# LEDCyrWheel.net
KiCad netlist of a schematic drawn in EAGLE
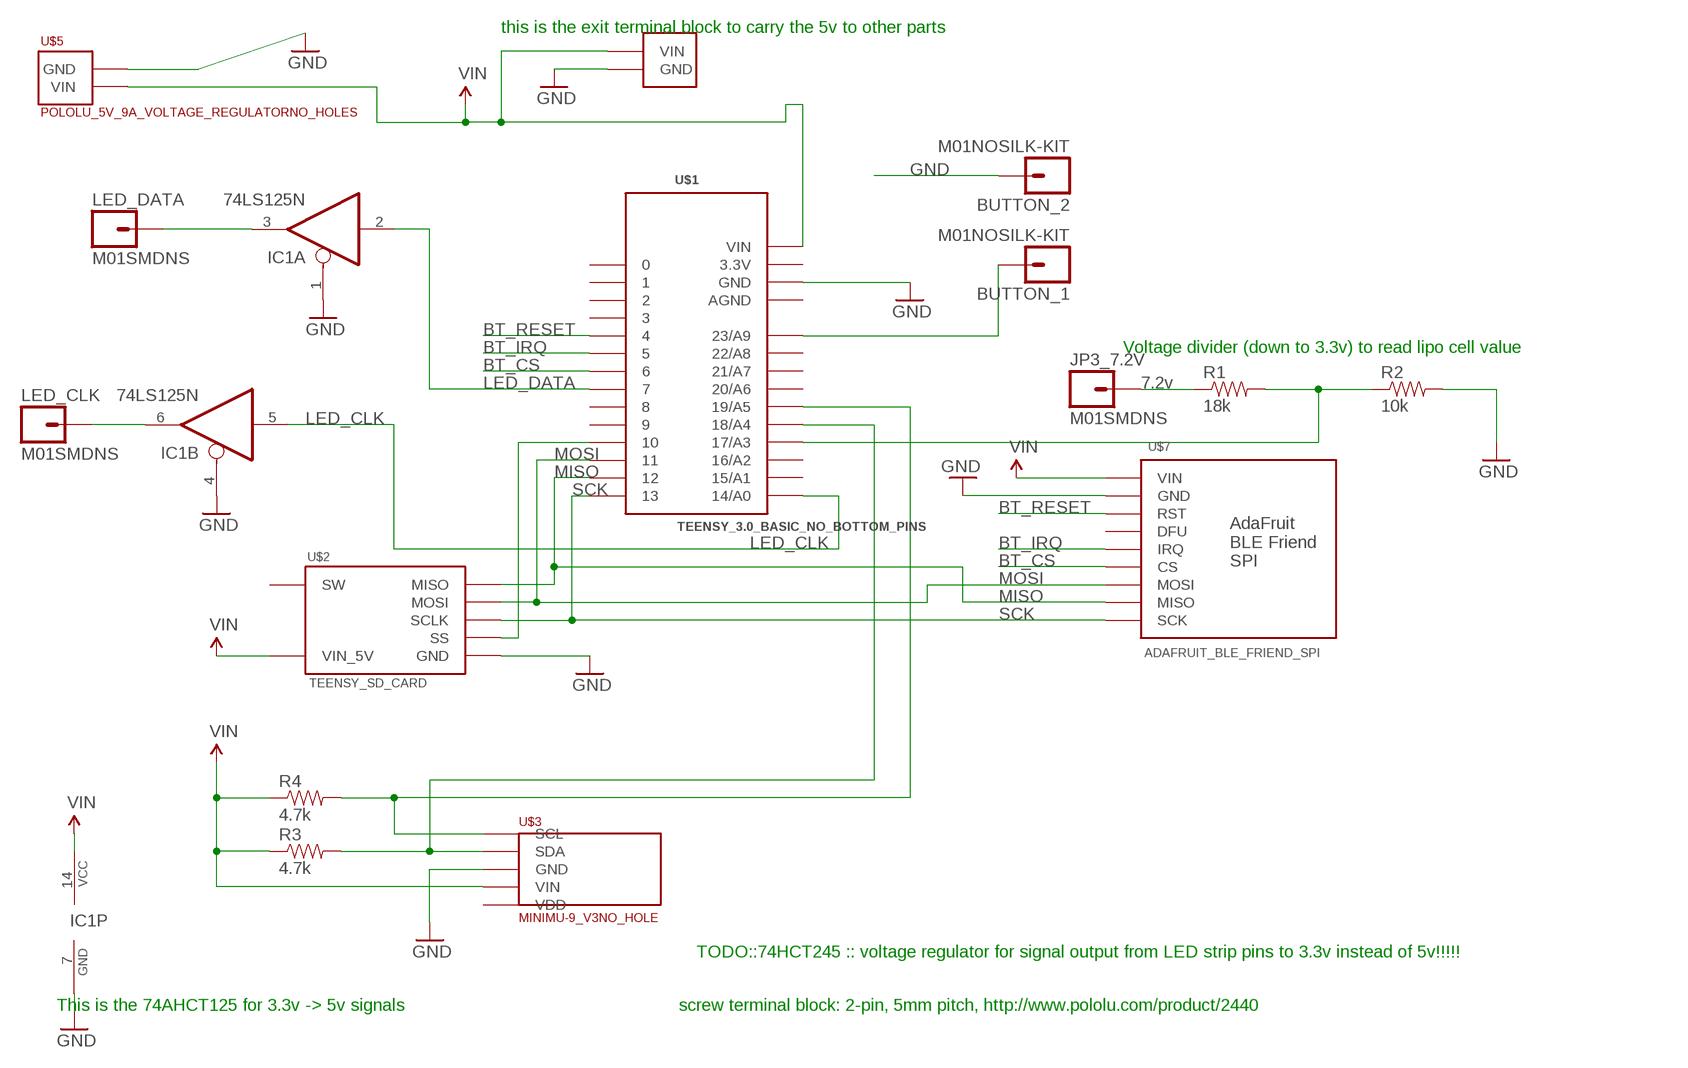
[diagram p0: schematic, sheet 1]

(export (version "E")
  (design (tool "Eeschema 10.0.6"))
  (components
    (comp (ref "BUTTON_1")
      (value "M01NOSILK-KIT")
      (footprint "eagle-import:1X01NS-KIT")
      (libsource (lib "eagle-import") (part "M01NOSILK-KIT"))
    )
    (comp (ref "BUTTON_2")
      (value "M01NOSILK-KIT")
      (footprint "eagle-import:1X01NS-KIT")
      (libsource (lib "eagle-import") (part "M01NOSILK-KIT"))
    )
    (comp (ref "IC1")
      (value "74LS125N")
      (footprint "eagle-import:DIL14")
      (libsource (lib "eagle-import") (part "74125NLS"))
    )
    (comp (ref "JP3_7.2V")
      (value "M01SMDNS")
      (footprint "eagle-import:1X01NS")
      (fields (field (name "VOLTAGE") "7.2v"))
      (libsource (lib "eagle-import") (part "M01SMDNS"))
    )
    (comp (ref "LED_CLK")
      (value "M01SMDNS")
      (footprint "eagle-import:1X01NS")
      (libsource (lib "eagle-import") (part "M01SMDNS"))
    )
    (comp (ref "LED_DATA")
      (value "M01SMDNS")
      (footprint "eagle-import:1X01NS")
      (libsource (lib "eagle-import") (part "M01SMDNS"))
    )
    (comp (ref "R1")
      (value "18k")
      (footprint "eagle-import:AXIAL-0.4")
      (libsource (lib "eagle-import") (part "RESISTORPTH-1/4W"))
    )
    (comp (ref "R2")
      (value "10k")
      (footprint "eagle-import:AXIAL-0.4")
      (libsource (lib "eagle-import") (part "RESISTORPTH-1/4W"))
    )
    (comp (ref "R3")
      (value "4.7k")
      (footprint "eagle-import:AXIAL-0.4")
      (libsource (lib "eagle-import") (part "RESISTORPTH-1/4W"))
    )
    (comp (ref "R4")
      (value "4.7k")
      (footprint "eagle-import:AXIAL-0.4")
      (libsource (lib "eagle-import") (part "RESISTORPTH-1/4W"))
    )
    (comp (ref "U$1")
      (value "TEENSY_3.0_BASIC_NO_BOTTOM_PINS")
      (footprint "eagle-import:TEENSY_3.0_BASIC_NO_BOTTOM_PINS")
      (libsource (lib "eagle-import") (part "TEENSY_3.0_BASIC_NO_BOTTOM_PINS"))
    )
    (comp (ref "U$2")
      (value "TEENSY_SD_CARD")
      (footprint "eagle-import:TEENSY_SD_CARD")
      (libsource (lib "eagle-import") (part "TEENSY_SD_CARD"))
    )
    (comp (ref "U$3")
      (value "MINIMU-9_V3NO_HOLE")
      (footprint "eagle-import:MINIMU-9_V3_NO_HOLE")
      (libsource (lib "eagle-import") (part "MINIMU-9_V3NO_HOLE"))
    )
    (comp (ref "U$5")
      (value "POLOLU_5V_9A_VOLTAGE_REGULATORNO_HOLES")
      (footprint "eagle-import:POLOLU_5V_9A_VOLTAGE_REGULATOR_NO_HOLES")
      (libsource (lib "eagle-import") (part "POLOLU_5V_9A_VOLTAGE_REGULATORNO_HOLES"))
    )
    (comp (ref "U$6")
      (value "VIN_GND_HOLE")
      (footprint "eagle-import:VIN_HOLE")
      (libsource (lib "eagle-import") (part "VIN_GND_HOLE"))
    )
    (comp (ref "U$7")
      (value "ADAFRUIT_BLE_FRIEND_SPI")
      (footprint "eagle-import:ADAFRUIT_BLE_FRIEND_SPI")
      (libsource (lib "eagle-import") (part "ADAFRUIT_BLE_FRIEND_SPI"))
    )
  )
  (nets
    (net (code "1") (name "/3.3V") (class "Default")
      (node (ref "U$1") (pin "3.3V") (pinfunction "3.3V_3.3V") (pintype "power_in"))
    )
    (net (code "2") (name "/AGND") (class "Default")
      (node (ref "U$1") (pin "AGND") (pinfunction "AGND_AGND") (pintype "power_in"))
    )
    (net (code "3") (name "/BT_CS") (class "Default")
      (node (ref "U$1") (pin "6") (pinfunction "6_6") (pintype "bidirectional"))
      (node (ref "U$7") (pin "CS") (pinfunction "CS_CS") (pintype "bidirectional"))
    )
    (net (code "4") (name "/BT_IRQ") (class "Default")
      (node (ref "U$1") (pin "5") (pinfunction "5_5") (pintype "bidirectional"))
      (node (ref "U$7") (pin "IRQ") (pinfunction "IRQ_IRQ") (pintype "bidirectional"))
    )
    (net (code "5") (name "/BT_RESET") (class "Default")
      (node (ref "U$1") (pin "4") (pinfunction "4_4") (pintype "bidirectional"))
      (node (ref "U$7") (pin "RST") (pinfunction "RST_RST") (pintype "bidirectional"))
    )
    (net (code "6") (name "/LED_CLK") (class "Default")
      (node (ref "IC1") (pin "5") (pinfunction "I_5") (pintype "input"))
      (node (ref "U$1") (pin "14/A0") (pinfunction "14/A0_14/A0") (pintype "bidirectional"))
    )
    (net (code "7") (name "/LED_DATA") (class "Default")
      (node (ref "IC1") (pin "2") (pinfunction "I_2") (pintype "input"))
      (node (ref "U$1") (pin "7") (pinfunction "7_7") (pintype "bidirectional"))
    )
    (net (code "8") (name "/MISO") (class "Default")
      (node (ref "U$1") (pin "12") (pinfunction "12_12") (pintype "bidirectional"))
      (node (ref "U$2") (pin "MISO") (pinfunction "MISO_MISO") (pintype "bidirectional"))
      (node (ref "U$7") (pin "MISO") (pinfunction "MISO_MISO") (pintype "bidirectional"))
    )
    (net (code "9") (name "/MOSI") (class "Default")
      (node (ref "U$1") (pin "11") (pinfunction "11_11") (pintype "bidirectional"))
      (node (ref "U$2") (pin "MOSI") (pinfunction "MOSI_MOSI") (pintype "bidirectional"))
      (node (ref "U$7") (pin "MOSI") (pinfunction "MOSI_MOSI") (pintype "bidirectional"))
    )
    (net (code "10") (name "/SCK") (class "Default")
      (node (ref "U$1") (pin "13") (pinfunction "13_13") (pintype "bidirectional"))
      (node (ref "U$2") (pin "SCLK") (pinfunction "SCLK_SCLK") (pintype "bidirectional"))
      (node (ref "U$7") (pin "SCK") (pinfunction "SCK_SCK") (pintype "bidirectional"))
    )
    (net (code "11") (name "GND") (class "Default")
      (node (ref "BUTTON_2") (pin "1") (pinfunction "1_1") (pintype "passive"))
      (node (ref "IC1") (pin "1") (pinfunction "OE_1") (pintype "input"))
      (node (ref "IC1") (pin "4") (pinfunction "OE_4") (pintype "input"))
      (node (ref "IC1") (pin "7") (pinfunction "GND_7") (pintype "power_in"))
      (node (ref "R2") (pin "P$2") (pinfunction "2_P$2") (pintype "passive"))
      (node (ref "U$1") (pin "GND") (pinfunction "GND_GND") (pintype "power_in"))
      (node (ref "U$2") (pin "GND") (pinfunction "GND_GND") (pintype "power_in"))
      (node (ref "U$3") (pin "GND") (pinfunction "GND_GND") (pintype "power_in"))
      (node (ref "U$5") (pin "GND") (pinfunction "GND_GND") (pintype "power_in"))
      (node (ref "U$5") (pin "GND2") (pinfunction "GND_GND2") (pintype "power_in"))
      (node (ref "U$5") (pin "GND3") (pinfunction "GND_GND3") (pintype "power_in"))
      (node (ref "U$6") (pin "GND") (pinfunction "GND_GND") (pintype "power_in"))
      (node (ref "U$7") (pin "GND") (pinfunction "GND_GND") (pintype "power_in"))
    )
    (net (code "12") (name "Net-(BUTTON_1-Pad1)") (class "Default")
      (node (ref "BUTTON_1") (pin "1") (pinfunction "1_1") (pintype "passive"))
      (node (ref "U$1") (pin "23/A9") (pinfunction "23/A9_23/A9") (pintype "bidirectional"))
    )
    (net (code "13") (name "Net-(IC1A-O)") (class "Default")
      (node (ref "IC1") (pin "3") (pinfunction "O_3") (pintype "tri_state"))
      (node (ref "LED_DATA") (pin "1") (pinfunction "1_1") (pintype "passive"))
    )
    (net (code "14") (name "Net-(IC1B-O)") (class "Default")
      (node (ref "IC1") (pin "6") (pinfunction "O_6") (pintype "tri_state"))
      (node (ref "LED_CLK") (pin "1") (pinfunction "1_1") (pintype "passive"))
    )
    (net (code "15") (name "Net-(R1-1)") (class "Default")
      (node (ref "JP3_7.2V") (pin "1") (pinfunction "1_1") (pintype "passive"))
      (node (ref "R1") (pin "P$1") (pinfunction "1_P$1") (pintype "passive"))
    )
    (net (code "16") (name "Net-(R1-2)") (class "Default")
      (node (ref "R1") (pin "P$2") (pinfunction "2_P$2") (pintype "passive"))
      (node (ref "R2") (pin "P$1") (pinfunction "1_P$1") (pintype "passive"))
      (node (ref "U$1") (pin "17/A3") (pinfunction "17/A3_17/A3") (pintype "bidirectional"))
    )
    (net (code "17") (name "Net-(R3-2)") (class "Default")
      (node (ref "R3") (pin "P$2") (pinfunction "2_P$2") (pintype "passive"))
      (node (ref "U$1") (pin "18/A4") (pinfunction "18/A4_18/A4") (pintype "bidirectional"))
      (node (ref "U$3") (pin "SDA") (pinfunction "SDA_SDA") (pintype "bidirectional"))
    )
    (net (code "18") (name "Net-(R4-2)") (class "Default")
      (node (ref "R4") (pin "P$2") (pinfunction "2_P$2") (pintype "passive"))
      (node (ref "U$1") (pin "19/A5") (pinfunction "19/A5_19/A5") (pintype "bidirectional"))
      (node (ref "U$3") (pin "SCL") (pinfunction "SCL_SCL") (pintype "bidirectional"))
    )
    (net (code "19") (name "Net-(U$1-Pad10)") (class "Default")
      (node (ref "U$1") (pin "10") (pinfunction "10_10") (pintype "bidirectional"))
      (node (ref "U$2") (pin "SS") (pinfunction "SS_SS") (pintype "bidirectional"))
    )
    (net (code "20") (name "VIN") (class "Default")
      (node (ref "IC1") (pin "14") (pinfunction "VCC_14") (pintype "power_in"))
      (node (ref "R3") (pin "P$1") (pinfunction "1_P$1") (pintype "passive"))
      (node (ref "R4") (pin "P$1") (pinfunction "1_P$1") (pintype "passive"))
      (node (ref "U$1") (pin "VIN") (pinfunction "VIN_VIN") (pintype "power_in"))
      (node (ref "U$2") (pin "VIN") (pinfunction "VIN_5V_VIN") (pintype "power_in"))
      (node (ref "U$3") (pin "VIN") (pinfunction "VIN_VIN") (pintype "bidirectional"))
      (node (ref "U$5") (pin "VIN") (pinfunction "VIN_VIN") (pintype "power_in"))
      (node (ref "U$5") (pin "VIN2") (pinfunction "VIN_VIN2") (pintype "power_in"))
      (node (ref "U$5") (pin "VIN3") (pinfunction "VIN_VIN3") (pintype "power_in"))
      (node (ref "U$6") (pin "VIN") (pinfunction "VIN_VIN") (pintype "power_in"))
      (node (ref "U$7") (pin "VIN") (pinfunction "VIN_VIN") (pintype "power_in"))
    )
    (net (code "21") (name "unconnected-(U$1-Pad0)") (class "Default")
      (node (ref "U$1") (pin "0") (pinfunction "0_0") (pintype "bidirectional"))
    )
    (net (code "22") (name "unconnected-(U$1-Pad1)") (class "Default")
      (node (ref "U$1") (pin "1") (pinfunction "1_1") (pintype "bidirectional"))
    )
    (net (code "23") (name "unconnected-(U$1-Pad2)") (class "Default")
      (node (ref "U$1") (pin "2") (pinfunction "2_2") (pintype "bidirectional"))
    )
    (net (code "24") (name "unconnected-(U$1-Pad3)") (class "Default")
      (node (ref "U$1") (pin "3") (pinfunction "3_3") (pintype "bidirectional"))
    )
    (net (code "25") (name "unconnected-(U$1-Pad8)") (class "Default")
      (node (ref "U$1") (pin "8") (pinfunction "8_8") (pintype "bidirectional"))
    )
    (net (code "26") (name "unconnected-(U$1-Pad9)") (class "Default")
      (node (ref "U$1") (pin "9") (pinfunction "9_9") (pintype "bidirectional"))
    )
    (net (code "27") (name "unconnected-(U$1-Pad15{slash}A1)") (class "Default")
      (node (ref "U$1") (pin "15/A1") (pinfunction "15/A1_15/A1") (pintype "bidirectional"))
    )
    (net (code "28") (name "unconnected-(U$1-Pad16{slash}A2)") (class "Default")
      (node (ref "U$1") (pin "16/A2") (pinfunction "16/A2_16/A2") (pintype "bidirectional"))
    )
    (net (code "29") (name "unconnected-(U$1-Pad20{slash}A6)") (class "Default")
      (node (ref "U$1") (pin "20/A6") (pinfunction "20/A6_20/A6") (pintype "bidirectional"))
    )
    (net (code "30") (name "unconnected-(U$1-Pad21{slash}A7)") (class "Default")
      (node (ref "U$1") (pin "21/A7") (pinfunction "21/A7_21/A7") (pintype "bidirectional"))
    )
    (net (code "31") (name "unconnected-(U$1-Pad22{slash}A8)") (class "Default")
      (node (ref "U$1") (pin "22/A8") (pinfunction "22/A8_22/A8") (pintype "bidirectional"))
    )
    (net (code "32") (name "unconnected-(U$2-PadSW)") (class "Default")
      (node (ref "U$2") (pin "SW") (pinfunction "SW_SW") (pintype "bidirectional"))
    )
    (net (code "33") (name "unconnected-(U$3-PadVDD)") (class "Default")
      (node (ref "U$3") (pin "VDD") (pinfunction "VDD_VDD") (pintype "bidirectional"))
    )
    (net (code "34") (name "unconnected-(U$7-PadDFU)") (class "Default")
      (node (ref "U$7") (pin "DFU") (pinfunction "DFU_DFU") (pintype "bidirectional"))
    )
  )
)
